# PTT_Mic_Filter.net
KiCad netlist of a schematic drawn in Altium Designer
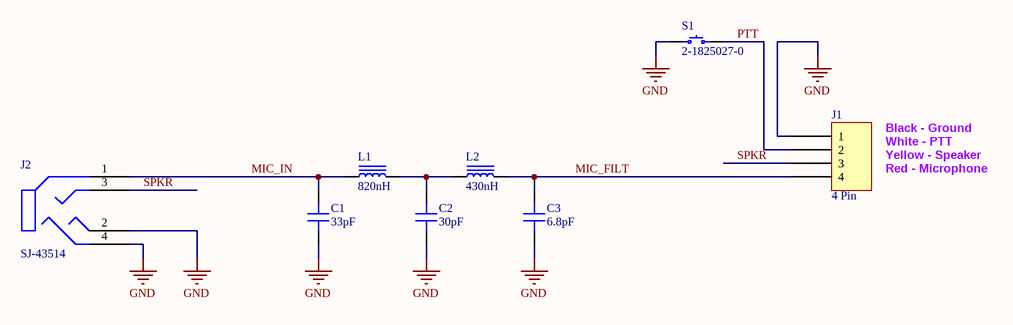
[diagram p0: PTT Mic Filter.SchDoc]

(export (version "E")
  (design (tool "Eeschema 10.0.6"))
  (components
    (comp (ref "C1")
      (value "33pF")
      (footprint "CAP 0603_1608")
      (description "CAP CER 33PF 50V C0G/NP0 0603")
      (fields (field (name "PART NUMBER") "06035A330KAT2A") (field (name "MANUFACTURER") "AVX Corporation"))
      (libsource (lib "altiumlibrary.com") (part "Capacitor"))
    )
    (comp (ref "C2")
      (value "30pF")
      (footprint "CAP 0603_1608")
      (description "CAP CER 30PF 50V C0G/NP0 0603")
      (fields
        (field (name "PART NUMBER") "CL10C300JB8NNNC")
        (field (name "MANUFACTURER") "Samsung Electro-Mechanics")
      )
      (libsource (lib "altiumlibrary.com") (part "Capacitor"))
    )
    (comp (ref "C3")
      (value "6.8pF")
      (footprint "CAP 0603_1608")
      (description "CAP CER 6.8PF 50V NP0 0603")
      (fields (field (name "PART NUMBER") "06035A6R8DAT2A") (field (name "MANUFACTURER") "AVX Corporation"))
      (libsource (lib "altiumlibrary.com") (part "Capacitor"))
    )
    (comp (ref "J1") (value "4 Pin") (footprint "Wire2Board") (libsource (lib "4 PIN") (part "4 Pin")))
    (comp (ref "J2")
      (value "SJ-43514")
      (footprint "CUI SJ-43514")
      (description "CONN JACK 4COND 3.5MM R/A")
      (fields (field (name "MANUFACTURER") "CUI Devices"))
      (libsource (lib "altiumlibrary.com") (part "CUI SJ-43514"))
    )
    (comp (ref "L1")
      (value "820nH")
      (footprint "IND 0603_1608 RF WW")
      (description "FIXED IND 820NH 730MA 176 MOHM")
      (fields (field (name "PART NUMBER") "BRC1608TR82M6") (field (name "MANUFACTURER") "Taiyo Yuden"))
      (libsource (lib "altiumlibrary.com") (part "Inductor"))
    )
    (comp (ref "L2")
      (value "430nH")
      (footprint "IND 0603_1608 RF WW")
      (description "FIXED IND 430NH 1.1A 82 MOHM SMD")
      (fields (field (name "PART NUMBER") "BRC1608TR43M6") (field (name "MANUFACTURER") "Taiyo Yuden"))
      (libsource (lib "altiumlibrary.com") (part "Inductor"))
    )
    (comp (ref "S1")
      (value "2-1825027-0")
      (footprint "TE 2-1825027-0")
      (description "SWITCH TACTILE SPST-NO 0.05A 24V")
      (fields (field (name "MANUFACTURER") "TE Connectivity ALCOSWITCH Switches"))
      (libsource (lib "altiumlibrary.com") (part "SPST-NO 2 PIN"))
    )
  )
  (nets
    (net (code "1") (name "/MIC_FILT") (class "Default")
      (node (ref "C3") (pin "2") (pinfunction "2_2") (pintype "passive"))
      (node (ref "J1") (pin "4") (pinfunction "4_4") (pintype "passive"))
      (node (ref "L2") (pin "2") (pinfunction "2_2") (pintype "passive"))
    )
    (net (code "2") (name "/MIC_IN") (class "Default")
      (node (ref "C1") (pin "2") (pinfunction "2_2") (pintype "passive"))
      (node (ref "J2") (pin "1") (pinfunction "SLEEVE_1") (pintype "passive"))
      (node (ref "L1") (pin "1") (pinfunction "1_1") (pintype "passive"))
    )
    (net (code "3") (name "/PTT") (class "Default")
      (node (ref "J1") (pin "2") (pinfunction "2_2") (pintype "passive"))
      (node (ref "S1") (pin "2") (pinfunction "2_2") (pintype "passive"))
    )
    (net (code "4") (name "/SPKR") (class "Default")
      (node (ref "J1") (pin "3") (pinfunction "3_3") (pintype "passive"))
      (node (ref "J2") (pin "3") (pinfunction "RING_1_3") (pintype "passive"))
    )
    (net (code "5") (name "GND") (class "Default")
      (node (ref "C1") (pin "1") (pinfunction "1_1") (pintype "passive"))
      (node (ref "C2") (pin "1") (pinfunction "1_1") (pintype "passive"))
      (node (ref "C3") (pin "1") (pinfunction "1_1") (pintype "passive"))
      (node (ref "J1") (pin "1") (pinfunction "1_1") (pintype "passive"))
      (node (ref "J2") (pin "2") (pinfunction "TIP_2") (pintype "passive"))
      (node (ref "J2") (pin "4") (pinfunction "RING_2_4") (pintype "passive"))
      (node (ref "S1") (pin "1") (pinfunction "1_1") (pintype "passive"))
    )
    (net (code "6") (name "Net-(C2-Pad2)") (class "Default")
      (node (ref "C2") (pin "2") (pinfunction "2_2") (pintype "passive"))
      (node (ref "L1") (pin "2") (pinfunction "2_2") (pintype "passive"))
      (node (ref "L2") (pin "1") (pinfunction "1_1") (pintype "passive"))
    )
  )
)
